# Sound_Activation_Detector.net
KiCad netlist of a schematic drawn in EasyEDA
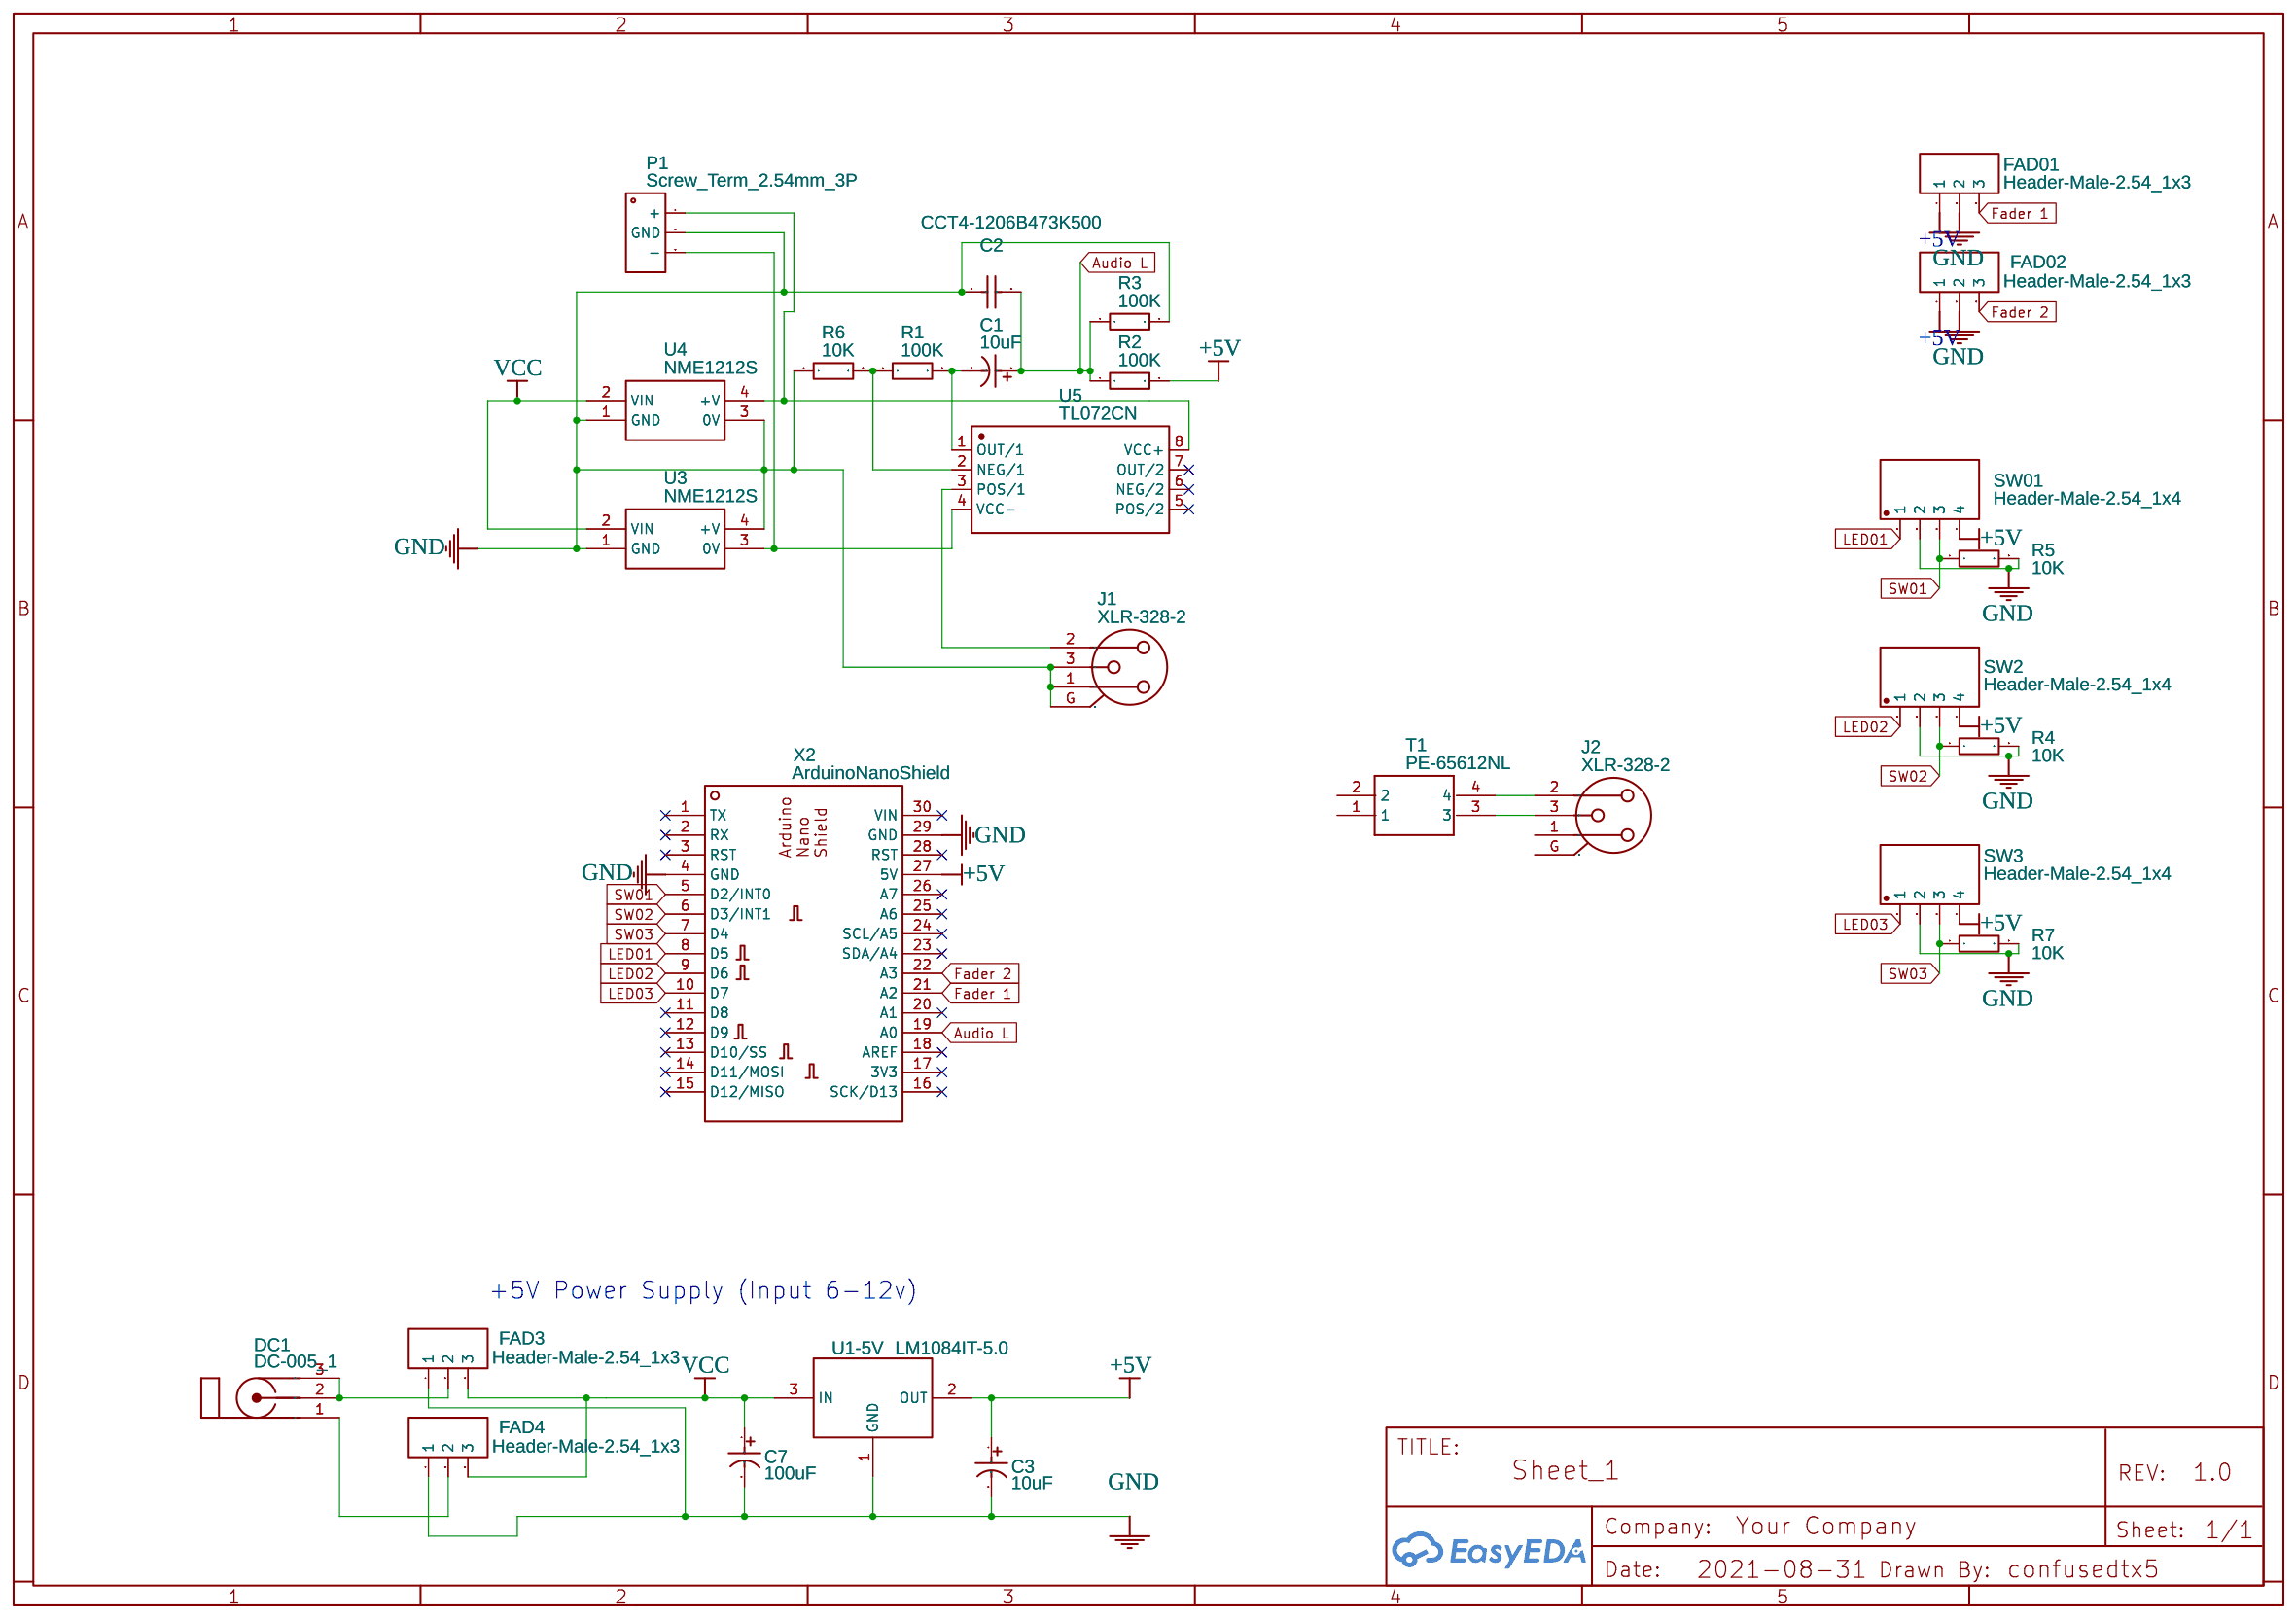
[diagram p0: schematic sheet]

(export (version "E")
  (design (tool "Eeschema 10.0.6"))
  (components
    (comp (ref "C1")
      (value "10uF")
      (fields (field (name "BOM_Manufacturer Part") "10uf/100V") (field (name "BOM_Supplier Part") "C2029"))
      (libsource (lib "") (part "10uf/100V"))
    )
    (comp (ref "C2")
      (value "CCT4-1206B473K500")
      (fields (field (name "BOM_Supplier Part") "C32275"))
      (libsource (lib "") (part "CCT4-1206B473K500"))
    )
    (comp (ref "C3")
      (value "10uF")
      (fields
        (field (name "BOM_Manufacturer Part") "10uF 25V RHOS")
        (field (name "BOM_Supplier Part") "C19576")
      )
      (libsource (lib "") (part "Unknown_495_-70"))
    )
    (comp (ref "C7")
      (value "100uF")
      (fields (field (name "BOM_Manufacturer Part") "100uF 25V") (field (name "BOM_Supplier Part") "C13376"))
      (libsource (lib "") (part "Unknown_370_-80"))
    )
    (comp (ref "DC1") (value "DC-005_1") (libsource (lib "") (part "Unknown_155_-105")))
    (comp (ref "FAD01")
      (value "Header-Male-2.54_1x3")
      (fields
        (field (name "BOM_Manufacturer Part") "Header2.54mm 1*3P")
        (field (name "BOM_Supplier Part") "C49257")
      )
      (libsource (lib "") (part "Header-Male-2.54_1x3"))
    )
    (comp (ref "FAD02")
      (value "Header-Male-2.54_1x3")
      (fields
        (field (name "BOM_Manufacturer Part") "Header2.54mm 1*3P")
        (field (name "BOM_Supplier Part") "C49257")
      )
      (libsource (lib "") (part "Header-Male-2.54_1x3"))
    )
    (comp (ref "FAD3")
      (value "Header-Male-2.54_1x3")
      (fields
        (field (name "BOM_Manufacturer Part") "Header2.54mm 1*3P")
        (field (name "BOM_Supplier Part") "C49257")
      )
      (libsource (lib "") (part "Header-Male-2.54_1x3"))
    )
    (comp (ref "FAD4")
      (value "Header-Male-2.54_1x3")
      (fields
        (field (name "BOM_Manufacturer Part") "Header2.54mm 1*3P")
        (field (name "BOM_Supplier Part") "C49257")
      )
      (libsource (lib "") (part "Header-Male-2.54_1x3"))
    )
    (comp (ref "J1")
      (value "XLR-328-2")
      (fields (field (name "BOM_Supplier Part") "C309331"))
      (libsource (lib "") (part "XLR-328-2"))
    )
    (comp (ref "J2")
      (value "XLR-328-2")
      (fields (field (name "BOM_Supplier Part") "C309331"))
      (libsource (lib "") (part "XLR-328-2"))
    )
    (comp (ref "P1")
      (value "Screw_Term_2.54mm_3P")
      (fields (field (name "BOM_Supplier Part") "undefined"))
      (libsource (lib "") (part "Screw_Term_2.54mm_3P"))
    )
    (comp (ref "R1")
      (value "100K")
      (fields
        (field (name "BOM_Manufacturer Part") "MFR0S2F1003A20")
        (field (name "BOM_Supplier Part") "C58589")
      )
      (libsource (lib "") (part "MFR0S2F1003A20"))
    )
    (comp (ref "R2")
      (value "100K")
      (fields
        (field (name "BOM_Manufacturer Part") "MFR0S2F1003A20")
        (field (name "BOM_Supplier Part") "C58589")
      )
      (libsource (lib "") (part "MFR0S2F1003A20"))
    )
    (comp (ref "R3")
      (value "100K")
      (fields
        (field (name "BOM_Manufacturer Part") "MFR0S2F1003A20")
        (field (name "BOM_Supplier Part") "C58589")
      )
      (libsource (lib "") (part "MFR0S2F1003A20"))
    )
    (comp (ref "R4")
      (value "10K")
      (fields (field (name "BOM_Supplier Part") "C119433"))
      (libsource (lib "") (part "MF1/2W-10KΩ±1% T52"))
    )
    (comp (ref "R5")
      (value "10K")
      (fields (field (name "BOM_Supplier Part") "C119433"))
      (libsource (lib "") (part "MF1/2W-10KΩ±1% T52"))
    )
    (comp (ref "R6")
      (value "10K")
      (fields (field (name "BOM_Supplier Part") "C119433"))
      (libsource (lib "") (part "MF1/2W-10KΩ±1% T52"))
    )
    (comp (ref "R7")
      (value "10K")
      (fields (field (name "BOM_Supplier Part") "C119433"))
      (libsource (lib "") (part "MF1/2W-10KΩ±1% T52"))
    )
    (comp (ref "SW01")
      (value "Header-Male-2.54_1x4")
      (fields
        (field (name "BOM_Manufacturer Part") "210S-1*4P L=11.6MMGold-plated black")
        (field (name "BOM_Supplier Part") "C124378")
      )
      (libsource (lib "") (part "Header-Male-2.54_1x4"))
    )
    (comp (ref "SW2")
      (value "Header-Male-2.54_1x4")
      (fields
        (field (name "BOM_Manufacturer Part") "210S-1*4P L=11.6MMGold-plated black")
        (field (name "BOM_Supplier Part") "C124378")
      )
      (libsource (lib "") (part "Header-Male-2.54_1x4"))
    )
    (comp (ref "SW3")
      (value "Header-Male-2.54_1x4")
      (fields
        (field (name "BOM_Manufacturer Part") "210S-1*4P L=11.6MMGold-plated black")
        (field (name "BOM_Supplier Part") "C124378")
      )
      (libsource (lib "") (part "Header-Male-2.54_1x4"))
    )
    (comp (ref "T1") (value "PE-65612NL") (libsource (lib "") (part "PE-65612NL")))
    (comp (ref "U1-5V")
      (value "LM1084IT-5.0")
      (fields (field (name "BOM_Supplier Part") "C9719"))
      (libsource (lib "") (part "LM1084IT-5.0"))
    )
    (comp (ref "U3") (value "NME1212S") (libsource (lib "") (part "NME1212S")))
    (comp (ref "U4") (value "NME1212S") (libsource (lib "") (part "NME1212S")))
    (comp (ref "U5")
      (value "TL072CN")
      (fields (field (name "BOM_Supplier Part") "C5164"))
      (libsource (lib "") (part "TL072CN"))
    )
    (comp (ref "X2") (value "ArduinoNanoShield") (libsource (lib "") (part "ArduinoNanoShield")))
  )
  (nets
    (net (code "1") (name "+5V") (class "Default")
      (node (ref "C3") (pin "1") (pinfunction "1_1") (pintype "input"))
      (node (ref "FAD01") (pin "1") (pinfunction "1_1") (pintype "input"))
      (node (ref "FAD02") (pin "1") (pinfunction "1_1") (pintype "input"))
      (node (ref "R2") (pin "2") (pinfunction "2_2") (pintype "input"))
      (node (ref "SW01") (pin "4") (pinfunction "4_4") (pintype "unspecified"))
      (node (ref "SW2") (pin "4") (pinfunction "4_4") (pintype "unspecified"))
      (node (ref "SW3") (pin "4") (pinfunction "4_4") (pintype "unspecified"))
      (node (ref "U1-5V") (pin "2") (pinfunction "OUT_2") (pintype "passive"))
      (node (ref "X2") (pin "27") (pinfunction "5V_27") (pintype "unspecified"))
    )
    (net (code "2") (name "Audio L") (class "Default")
      (node (ref "C1") (pin "1") (pinfunction "1_1") (pintype "input"))
      (node (ref "C2") (pin "2") (pinfunction "2_2") (pintype "input"))
      (node (ref "R2") (pin "1") (pinfunction "1_1") (pintype "input"))
      (node (ref "R3") (pin "1") (pinfunction "1_1") (pintype "input"))
      (node (ref "X2") (pin "19") (pinfunction "A0_19") (pintype "unspecified"))
    )
    (net (code "3") (name "Fader 1") (class "Default")
      (node (ref "FAD01") (pin "3") (pinfunction "3_3") (pintype "input"))
      (node (ref "X2") (pin "21") (pinfunction "A2_21") (pintype "unspecified"))
    )
    (net (code "4") (name "Fader 2") (class "Default")
      (node (ref "FAD02") (pin "3") (pinfunction "3_3") (pintype "input"))
      (node (ref "X2") (pin "22") (pinfunction "A3_22") (pintype "unspecified"))
    )
    (net (code "5") (name "GND") (class "Default")
      (node (ref "C2") (pin "1") (pinfunction "1_1") (pintype "input"))
      (node (ref "C3") (pin "2") (pinfunction "2_2") (pintype "input"))
      (node (ref "C7") (pin "2") (pinfunction "2_2") (pintype "input"))
      (node (ref "FAD01") (pin "2") (pinfunction "2_2") (pintype "input"))
      (node (ref "FAD02") (pin "2") (pinfunction "2_2") (pintype "input"))
      (node (ref "FAD3") (pin "1") (pinfunction "1_1") (pintype "input"))
      (node (ref "FAD4") (pin "1") (pinfunction "1_1") (pintype "input"))
      (node (ref "J1") (pin "1") (pinfunction "1_1") (pintype "unspecified"))
      (node (ref "J1") (pin "3") (pinfunction "3_3") (pintype "unspecified"))
      (node (ref "J1") (pin "G") (pinfunction "G_G") (pintype "unspecified"))
      (node (ref "P1") (pin "2") (pinfunction "GND_2") (pintype "unspecified"))
      (node (ref "R3") (pin "2") (pinfunction "2_2") (pintype "input"))
      (node (ref "R4") (pin "2") (pinfunction "2_2") (pintype "unspecified"))
      (node (ref "R5") (pin "2") (pinfunction "2_2") (pintype "unspecified"))
      (node (ref "R6") (pin "1") (pinfunction "1_1") (pintype "unspecified"))
      (node (ref "R7") (pin "2") (pinfunction "2_2") (pintype "unspecified"))
      (node (ref "SW01") (pin "2") (pinfunction "2_2") (pintype "unspecified"))
      (node (ref "SW2") (pin "2") (pinfunction "2_2") (pintype "unspecified"))
      (node (ref "SW3") (pin "2") (pinfunction "2_2") (pintype "unspecified"))
      (node (ref "U1-5V") (pin "1") (pinfunction "GND_1") (pintype "passive"))
      (node (ref "U3") (pin "1") (pinfunction "GND_1") (pintype "passive"))
      (node (ref "U3") (pin "4") (pinfunction "+V_4") (pintype "output"))
      (node (ref "U4") (pin "1") (pinfunction "GND_1") (pintype "passive"))
      (node (ref "U4") (pin "3") (pinfunction "0V_3") (pintype "output"))
      (node (ref "X2") (pin "29") (pinfunction "GND_29") (pintype "unspecified"))
      (node (ref "X2") (pin "4") (pinfunction "GND_4") (pintype "unspecified"))
    )
    (net (code "6") (name "LED01") (class "Default")
      (node (ref "SW01") (pin "1") (pinfunction "1_1") (pintype "unspecified"))
      (node (ref "X2") (pin "8") (pinfunction "D5_8") (pintype "unspecified"))
    )
    (net (code "7") (name "LED02") (class "Default")
      (node (ref "SW2") (pin "1") (pinfunction "1_1") (pintype "unspecified"))
      (node (ref "X2") (pin "9") (pinfunction "D6_9") (pintype "unspecified"))
    )
    (net (code "8") (name "LED03") (class "Default")
      (node (ref "SW3") (pin "1") (pinfunction "1_1") (pintype "unspecified"))
      (node (ref "X2") (pin "10") (pinfunction "D7_10") (pintype "unspecified"))
    )
    (net (code "9") (name "Net-(DC1-Pad1)") (class "Default")
      (node (ref "DC1") (pin "1") (pinfunction "1_1") (pintype "input"))
      (node (ref "FAD4") (pin "2") (pinfunction "2_2") (pintype "input"))
    )
    (net (code "10") (name "Net-(DC1-VCC)") (class "Default")
      (node (ref "DC1") (pin "2") (pinfunction "VCC_2") (pintype "input"))
      (node (ref "DC1") (pin "3") (pinfunction "3_3") (pintype "input"))
      (node (ref "FAD3") (pin "2") (pinfunction "2_2") (pintype "input"))
    )
    (net (code "11") (name "Net-(J2-Pad2)") (class "Default")
      (node (ref "J2") (pin "2") (pinfunction "2_2") (pintype "unspecified"))
      (node (ref "T1") (pin "4") (pinfunction "4_4") (pintype "bidirectional"))
    )
    (net (code "12") (name "Net-(J2-Pad3)") (class "Default")
      (node (ref "J2") (pin "3") (pinfunction "3_3") (pintype "unspecified"))
      (node (ref "T1") (pin "3") (pinfunction "3_3") (pintype "bidirectional"))
    )
    (net (code "13") (name "Net-(P1-+)") (class "Default")
      (node (ref "P1") (pin "1") (pinfunction "+_1") (pintype "unspecified"))
      (node (ref "U4") (pin "4") (pinfunction "+V_4") (pintype "output"))
      (node (ref "U5") (pin "8") (pinfunction "VCC+_8") (pintype "unspecified"))
    )
    (net (code "14") (name "Net-(P1--)") (class "Default")
      (node (ref "P1") (pin "3") (pinfunction "-_3") (pintype "unspecified"))
      (node (ref "U3") (pin "3") (pinfunction "0V_3") (pintype "output"))
      (node (ref "U5") (pin "4") (pinfunction "VCC-_4") (pintype "unspecified"))
    )
    (net (code "15") (name "Net-(U5-NEG{slash}1)") (class "Default")
      (node (ref "R1") (pin "1") (pinfunction "1_1") (pintype "input"))
      (node (ref "R6") (pin "2") (pinfunction "2_2") (pintype "unspecified"))
      (node (ref "U5") (pin "2") (pinfunction "NEG/1_2") (pintype "unspecified"))
    )
    (net (code "16") (name "Net-(U5-OUT{slash}1)") (class "Default")
      (node (ref "C1") (pin "2") (pinfunction "2_2") (pintype "input"))
      (node (ref "R1") (pin "2") (pinfunction "2_2") (pintype "input"))
      (node (ref "U5") (pin "1") (pinfunction "OUT/1_1") (pintype "unspecified"))
    )
    (net (code "17") (name "Net-(U5-POS{slash}1)") (class "Default")
      (node (ref "J1") (pin "2") (pinfunction "2_2") (pintype "unspecified"))
      (node (ref "U5") (pin "3") (pinfunction "POS/1_3") (pintype "unspecified"))
    )
    (net (code "18") (name "SW01") (class "Default")
      (node (ref "R5") (pin "1") (pinfunction "1_1") (pintype "unspecified"))
      (node (ref "SW01") (pin "3") (pinfunction "3_3") (pintype "unspecified"))
      (node (ref "X2") (pin "5") (pinfunction "D2/INT0_5") (pintype "unspecified"))
    )
    (net (code "19") (name "SW02") (class "Default")
      (node (ref "R4") (pin "1") (pinfunction "1_1") (pintype "unspecified"))
      (node (ref "SW2") (pin "3") (pinfunction "3_3") (pintype "unspecified"))
      (node (ref "X2") (pin "6") (pinfunction "D3/INT1_6") (pintype "unspecified"))
    )
    (net (code "20") (name "SW03") (class "Default")
      (node (ref "R7") (pin "1") (pinfunction "1_1") (pintype "unspecified"))
      (node (ref "SW3") (pin "3") (pinfunction "3_3") (pintype "unspecified"))
      (node (ref "X2") (pin "7") (pinfunction "D4_7") (pintype "unspecified"))
    )
    (net (code "21") (name "VCC") (class "Default")
      (node (ref "C7") (pin "1") (pinfunction "1_1") (pintype "input"))
      (node (ref "FAD3") (pin "3") (pinfunction "3_3") (pintype "input"))
      (node (ref "FAD4") (pin "3") (pinfunction "3_3") (pintype "input"))
      (node (ref "U1-5V") (pin "3") (pinfunction "IN_3") (pintype "passive"))
      (node (ref "U3") (pin "2") (pinfunction "VIN_2") (pintype "passive"))
      (node (ref "U4") (pin "2") (pinfunction "VIN_2") (pintype "passive"))
    )
    (net (code "22") (name "unconnected-(J2-Pad1)") (class "Default")
      (node (ref "J2") (pin "1") (pinfunction "1_1") (pintype "unspecified"))
    )
    (net (code "23") (name "unconnected-(J2-PadG)") (class "Default")
      (node (ref "J2") (pin "G") (pinfunction "G_G") (pintype "unspecified"))
    )
    (net (code "24") (name "unconnected-(T1-Pad1)") (class "Default")
      (node (ref "T1") (pin "1") (pinfunction "1_1") (pintype "bidirectional"))
    )
    (net (code "25") (name "unconnected-(T1-Pad2)") (class "Default")
      (node (ref "T1") (pin "2") (pinfunction "2_2") (pintype "bidirectional"))
    )
    (net (code "26") (name "unconnected-(U5-NEG{slash}2-Pad6)") (class "Default")
      (node (ref "U5") (pin "6") (pinfunction "NEG/2_6") (pintype "unspecified+no_connect"))
    )
    (net (code "27") (name "unconnected-(U5-OUT{slash}2-Pad7)") (class "Default")
      (node (ref "U5") (pin "7") (pinfunction "OUT/2_7") (pintype "unspecified+no_connect"))
    )
    (net (code "28") (name "unconnected-(U5-POS{slash}2-Pad5)") (class "Default")
      (node (ref "U5") (pin "5") (pinfunction "POS/2_5") (pintype "unspecified+no_connect"))
    )
    (net (code "29") (name "unconnected-(X2-3V3-Pad17)") (class "Default")
      (node (ref "X2") (pin "17") (pinfunction "3V3_17") (pintype "unspecified+no_connect"))
    )
    (net (code "30") (name "unconnected-(X2-A1-Pad20)") (class "Default")
      (node (ref "X2") (pin "20") (pinfunction "A1_20") (pintype "unspecified+no_connect"))
    )
    (net (code "31") (name "unconnected-(X2-A6-Pad25)") (class "Default")
      (node (ref "X2") (pin "25") (pinfunction "A6_25") (pintype "unspecified+no_connect"))
    )
    (net (code "32") (name "unconnected-(X2-A7-Pad26)") (class "Default")
      (node (ref "X2") (pin "26") (pinfunction "A7_26") (pintype "unspecified+no_connect"))
    )
    (net (code "33") (name "unconnected-(X2-AREF-Pad18)") (class "Default")
      (node (ref "X2") (pin "18") (pinfunction "AREF_18") (pintype "unspecified+no_connect"))
    )
    (net (code "34") (name "unconnected-(X2-D8-Pad11)") (class "Default")
      (node (ref "X2") (pin "11") (pinfunction "D8_11") (pintype "unspecified+no_connect"))
    )
    (net (code "35") (name "unconnected-(X2-D9-Pad12)") (class "Default")
      (node (ref "X2") (pin "12") (pinfunction "D9_12") (pintype "unspecified+no_connect"))
    )
    (net (code "36") (name "unconnected-(X2-D10{slash}SS-Pad13)") (class "Default")
      (node (ref "X2") (pin "13") (pinfunction "D10/SS_13") (pintype "unspecified+no_connect"))
    )
    (net (code "37") (name "unconnected-(X2-D11{slash}MOSI-Pad14)") (class "Default")
      (node (ref "X2") (pin "14") (pinfunction "D11/MOSI_14") (pintype "unspecified+no_connect"))
    )
    (net (code "38") (name "unconnected-(X2-D12{slash}MISO-Pad15)") (class "Default")
      (node (ref "X2") (pin "15") (pinfunction "D12/MISO_15") (pintype "unspecified+no_connect"))
    )
    (net (code "39") (name "unconnected-(X2-RST-Pad3)") (class "Default")
      (node (ref "X2") (pin "3") (pinfunction "RST_3") (pintype "unspecified+no_connect"))
    )
    (net (code "40") (name "unconnected-(X2-RST-Pad28)") (class "Default")
      (node (ref "X2") (pin "28") (pinfunction "RST_28") (pintype "unspecified+no_connect"))
    )
    (net (code "41") (name "unconnected-(X2-RX-Pad2)") (class "Default")
      (node (ref "X2") (pin "2") (pinfunction "RX_2") (pintype "unspecified+no_connect"))
    )
    (net (code "42") (name "unconnected-(X2-SCK{slash}D13-Pad16)") (class "Default")
      (node (ref "X2") (pin "16") (pinfunction "SCK/D13_16") (pintype "unspecified+no_connect"))
    )
    (net (code "43") (name "unconnected-(X2-SCL{slash}A5-Pad24)") (class "Default")
      (node (ref "X2") (pin "24") (pinfunction "SCL/A5_24") (pintype "unspecified+no_connect"))
    )
    (net (code "44") (name "unconnected-(X2-SDA{slash}A4-Pad23)") (class "Default")
      (node (ref "X2") (pin "23") (pinfunction "SDA/A4_23") (pintype "unspecified+no_connect"))
    )
    (net (code "45") (name "unconnected-(X2-TX-Pad1)") (class "Default")
      (node (ref "X2") (pin "1") (pinfunction "TX_1") (pintype "unspecified+no_connect"))
    )
    (net (code "46") (name "unconnected-(X2-VIN-Pad30)") (class "Default")
      (node (ref "X2") (pin "30") (pinfunction "VIN_30") (pintype "unspecified+no_connect"))
    )
  )
)
